# cpLeoNode_V3_0.net
KiCad netlist of a schematic drawn in EAGLE
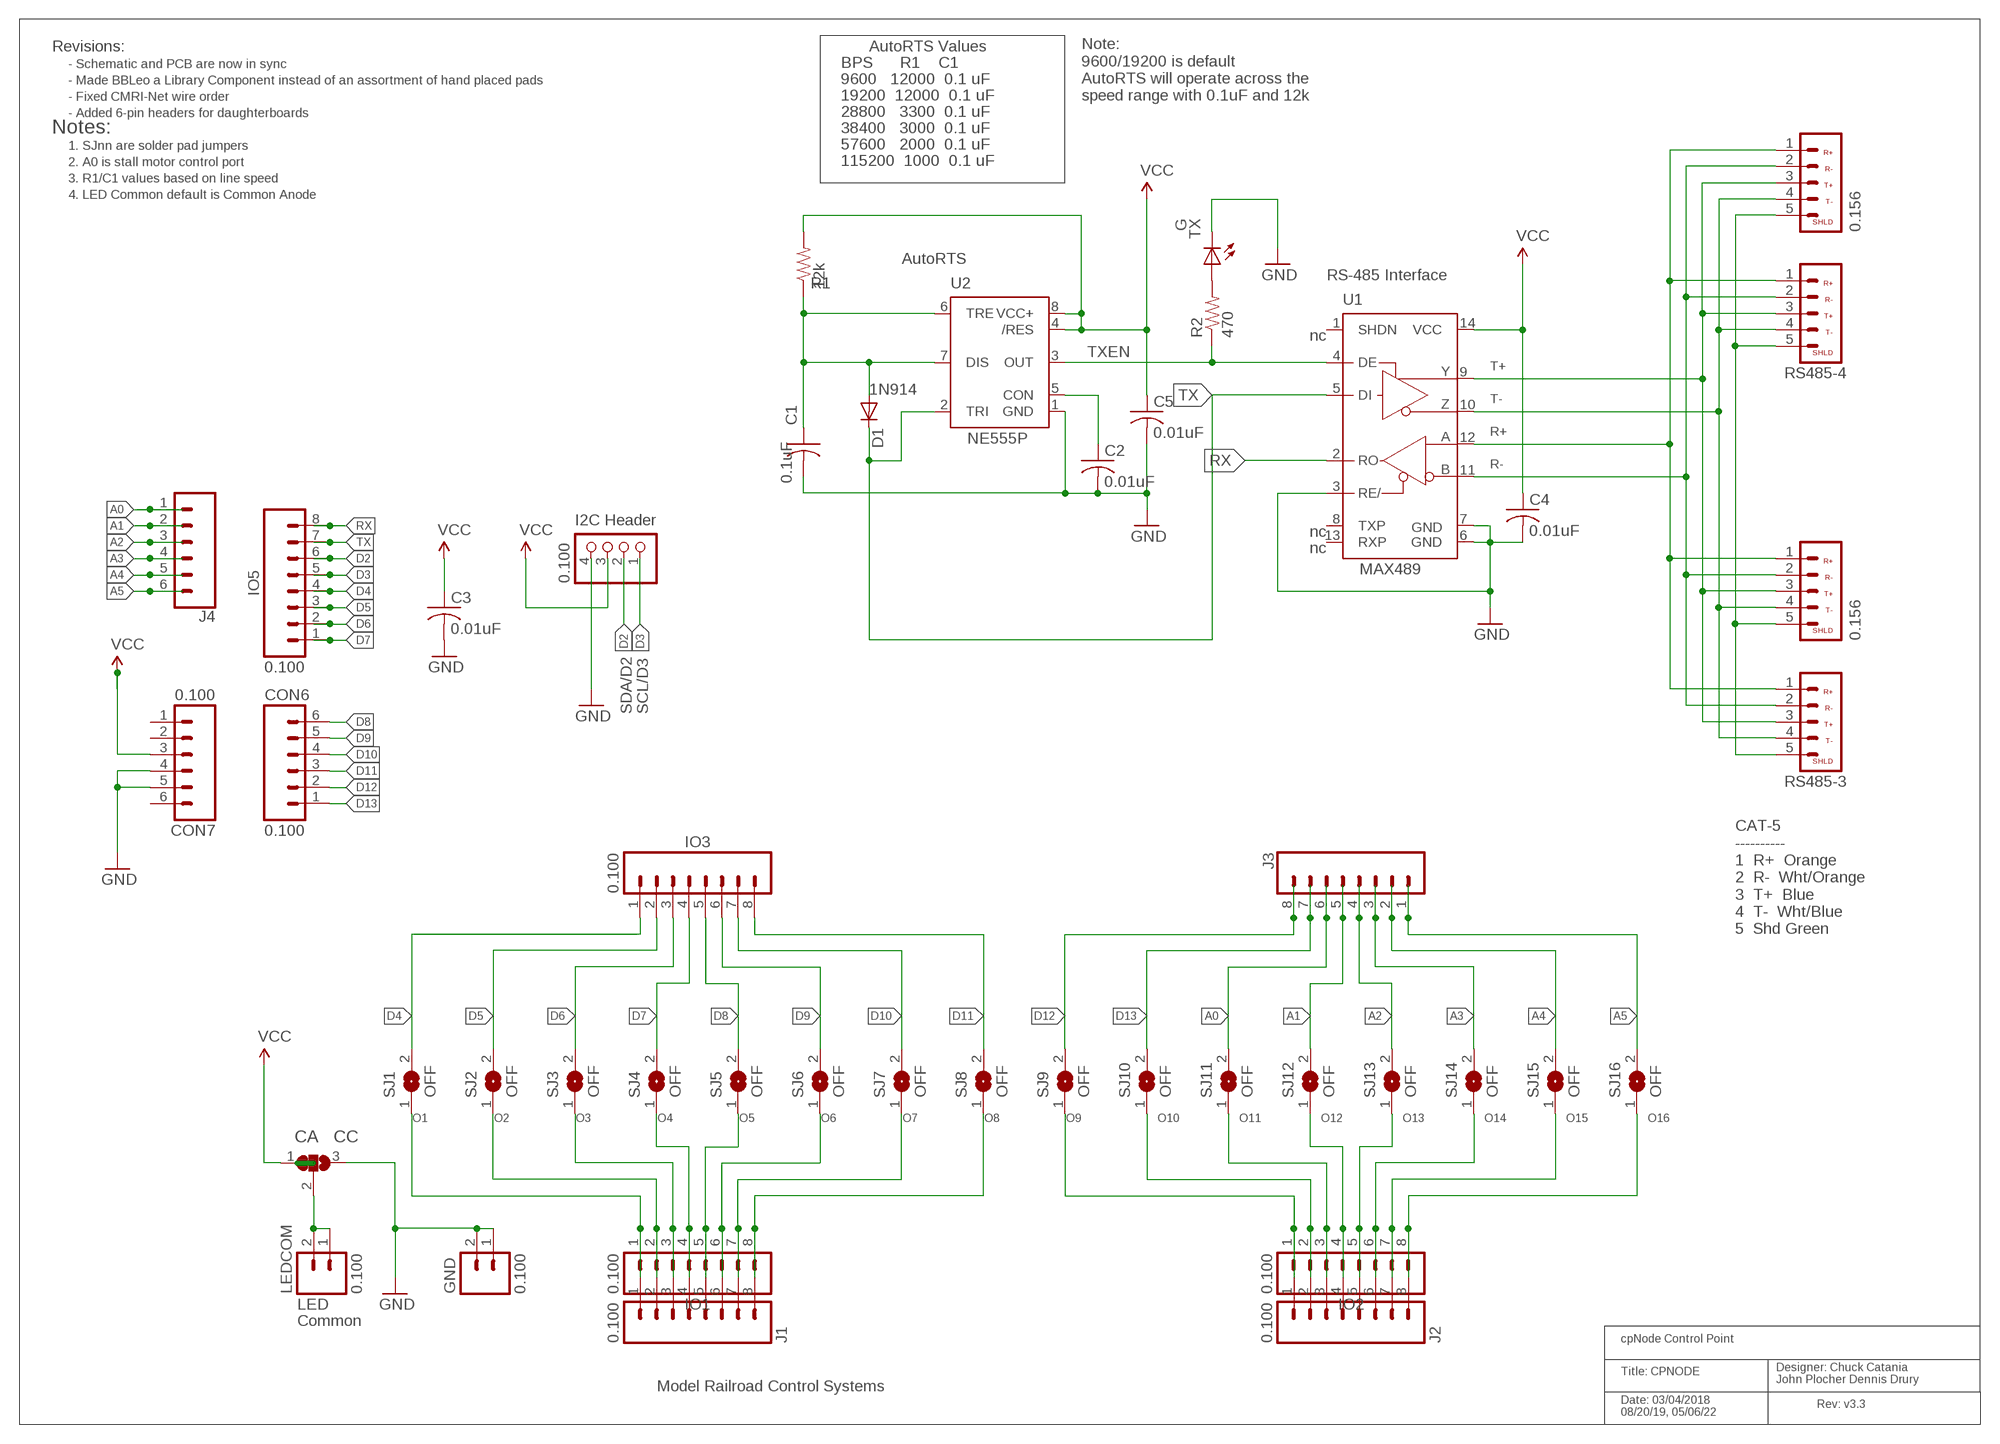
[diagram p0: schematic, sheet 1]

(export (version "E")
  (design (tool "Eeschema 10.0.6"))
  (components
    (comp (ref "C1")
      (value "0.1uF")
      (footprint "eagle-import:C-PTH-0.100")
      (libsource (lib "eagle-import") (part "CAPPTH2"))
    )
    (comp (ref "C2")
      (value "0.01uF")
      (footprint "eagle-import:C-PTH-0.100")
      (libsource (lib "eagle-import") (part "CAPPTH2"))
    )
    (comp (ref "C3")
      (value "0.01uF")
      (footprint "eagle-import:C-PTH-0.100")
      (libsource (lib "eagle-import") (part "CAPPTH2"))
    )
    (comp (ref "C4")
      (value "0.01uF")
      (footprint "eagle-import:C-PTH-0.100")
      (libsource (lib "eagle-import") (part "CAPPTH2"))
    )
    (comp (ref "C5")
      (value "0.01uF")
      (footprint "eagle-import:C-PTH-0.100")
      (libsource (lib "eagle-import") (part "CAPPTH2"))
    )
    (comp (ref "CON6")
      (value "0.100")
      (footprint "eagle-import:1X06-SIP_LOCK")
      (libsource (lib "eagle-import") (part "CONNECTOR-M06SIP_LOCK"))
    )
    (comp (ref "CON7")
      (value "0.100")
      (footprint "eagle-import:1X06-SIP_LOCK")
      (libsource (lib "eagle-import") (part "CONNECTOR-M06SIP_LOCK"))
    )
    (comp (ref "D1")
      (value "1N4148")
      (footprint "eagle-import:DIODE-1N4148")
      (libsource (lib "eagle-import") (part "DIODE1N4148"))
    )
    (comp (ref "GND")
      (value "0.100")
      (footprint "eagle-import:MOLEX-1X2_LOCK")
      (libsource (lib "eagle-import") (part "M02POLAR_LOCK"))
    )
    (comp (ref "I2CHDR")
      (value "0.100")
      (footprint "eagle-import:1X04_90")
      (libsource (lib "eagle-import") (part "PINHD-1X4/90"))
    )
    (comp (ref "IO1")
      (value "0.100")
      (footprint "eagle-import:1X08")
      (libsource (lib "eagle-import") (part "M081X08"))
    )
    (comp (ref "IO2")
      (value "0.100")
      (footprint "eagle-import:1X08")
      (libsource (lib "eagle-import") (part "M081X08"))
    )
    (comp (ref "IO3")
      (value "0.100")
      (footprint "eagle-import:1X08")
      (libsource (lib "eagle-import") (part "M081X08"))
    )
    (comp (ref "IO5")
      (value "0.100")
      (footprint "eagle-import:1X08")
      (libsource (lib "eagle-import") (part "M081X08"))
    )
    (comp (ref "J1")
      (value "0.100")
      (footprint "eagle-import:1X08_LOCK_LONGPADS")
      (libsource (lib "eagle-import") (part "CONNECTOR-M08LOCK_LONGPADS"))
    )
    (comp (ref "J2")
      (value "0.100")
      (footprint "eagle-import:1X08_LOCK_LONGPADS")
      (libsource (lib "eagle-import") (part "CONNECTOR-M08LOCK_LONGPADS"))
    )
    (comp (ref "J3")
      (value "CONN_08\"")
      (footprint "eagle-import:1X08")
      (libsource (lib "eagle-import") (part "CONN_08{dblquote}"))
    )
    (comp (ref "J4")
      (value "CONN_06SILK_FEMALE_PTH")
      (footprint "eagle-import:1X06")
      (libsource (lib "eagle-import") (part "CONN_06SILK_FEMALE_PTH"))
    )
    (comp (ref "LEDCOM")
      (value "0.100")
      (footprint "eagle-import:MOLEX-1X2_LOCK")
      (libsource (lib "eagle-import") (part "M02POLAR_LOCK"))
    )
    (comp (ref "P1")
      (value "CA CC")
      (footprint "eagle-import:3P-SMD-2X4.8")
      (libsource (lib "eagle-import") (part "PAD-SOLDERJUMPER-2WAYT"))
    )
    (comp (ref "R1")
      (value "12k")
      (footprint "eagle-import:AXIAL-0.4-RES")
      (libsource (lib "eagle-import") (part "RPTH04"))
    )
    (comp (ref "R2")
      (value "470")
      (footprint "eagle-import:AXIAL-0.4-RES")
      (libsource (lib "eagle-import") (part "RPTH04"))
    )
    (comp (ref "RS485-1")
      (value "0.156")
      (footprint "eagle-import:KK-156-5")
      (libsource (lib "eagle-import") (part "CONNECTOR-CMRINET.156"))
    )
    (comp (ref "RS485-2")
      (value "0.156")
      (footprint "eagle-import:KK-156-5")
      (libsource (lib "eagle-import") (part "CONNECTOR-CMRINET.156"))
    )
    (comp (ref "RS485-3")
      (value "3.5mm")
      (footprint "eagle-import:CMRINET-3.5MM")
      (libsource (lib "eagle-import") (part "CONNECTOR-CMRINET3.5MM"))
    )
    (comp (ref "RS485-4")
      (value "3.5mm")
      (footprint "eagle-import:CMRINET-3.5MM")
      (libsource (lib "eagle-import") (part "CONNECTOR-CMRINET3.5MM"))
    )
    (comp (ref "SJ1")
      (value "OFF")
      (footprint "eagle-import:SJ")
      (libsource (lib "eagle-import") (part "SJ"))
    )
    (comp (ref "SJ2")
      (value "OFF")
      (footprint "eagle-import:SJ")
      (libsource (lib "eagle-import") (part "SJ"))
    )
    (comp (ref "SJ3")
      (value "OFF")
      (footprint "eagle-import:SJ")
      (libsource (lib "eagle-import") (part "SJ"))
    )
    (comp (ref "SJ4")
      (value "OFF")
      (footprint "eagle-import:SJ")
      (libsource (lib "eagle-import") (part "SJ"))
    )
    (comp (ref "SJ5")
      (value "OFF")
      (footprint "eagle-import:SJ")
      (libsource (lib "eagle-import") (part "SJ"))
    )
    (comp (ref "SJ6")
      (value "OFF")
      (footprint "eagle-import:SJ")
      (libsource (lib "eagle-import") (part "SJ"))
    )
    (comp (ref "SJ7")
      (value "OFF")
      (footprint "eagle-import:SJ")
      (libsource (lib "eagle-import") (part "SJ"))
    )
    (comp (ref "SJ8")
      (value "OFF")
      (footprint "eagle-import:SJ")
      (libsource (lib "eagle-import") (part "SJ"))
    )
    (comp (ref "SJ9")
      (value "OFF")
      (footprint "eagle-import:SJ")
      (libsource (lib "eagle-import") (part "SJ"))
    )
    (comp (ref "SJ10")
      (value "OFF")
      (footprint "eagle-import:SJ")
      (libsource (lib "eagle-import") (part "SJ"))
    )
    (comp (ref "SJ11")
      (value "OFF")
      (footprint "eagle-import:SJ")
      (libsource (lib "eagle-import") (part "SJ"))
    )
    (comp (ref "SJ12")
      (value "OFF")
      (footprint "eagle-import:SJ")
      (libsource (lib "eagle-import") (part "SJ"))
    )
    (comp (ref "SJ13")
      (value "OFF")
      (footprint "eagle-import:SJ")
      (libsource (lib "eagle-import") (part "SJ"))
    )
    (comp (ref "SJ14")
      (value "OFF")
      (footprint "eagle-import:SJ")
      (libsource (lib "eagle-import") (part "SJ"))
    )
    (comp (ref "SJ15")
      (value "OFF")
      (footprint "eagle-import:SJ")
      (libsource (lib "eagle-import") (part "SJ"))
    )
    (comp (ref "SJ16")
      (value "OFF")
      (footprint "eagle-import:SJ")
      (libsource (lib "eagle-import") (part "SJ"))
    )
    (comp (ref "TX")
      (value "G")
      (footprint "eagle-import:LED3MM")
      (libsource (lib "eagle-import") (part "LEDLED3MM"))
    )
    (comp (ref "U1")
      (value "MAX3465CPD")
      (footprint "eagle-import:DIL14")
      (fields (field (name "MPN") "MAX3465CPD+"))
      (libsource (lib "eagle-import") (part "MAX346PD5C"))
    )
    (comp (ref "U2")
      (value "NE555P")
      (footprint "eagle-import:DIL-08")
      (fields (field (name "MF") "Arrow Electronics") (field (name "MPN") "NE555N"))
      (libsource (lib "eagle-import") (part "NE555P"))
    )
  )
  (nets
    (net (code "1") (name "/O1") (class "Default")
      (node (ref "IO1") (pin "1") (pinfunction "1_1") (pintype "passive"))
      (node (ref "J1") (pin "1") (pinfunction "1_1") (pintype "passive"))
      (node (ref "SJ1") (pin "1") (pinfunction "1_1") (pintype "passive"))
    )
    (net (code "2") (name "/O2") (class "Default")
      (node (ref "IO1") (pin "2") (pinfunction "2_2") (pintype "passive"))
      (node (ref "J1") (pin "2") (pinfunction "2_2") (pintype "passive"))
      (node (ref "SJ2") (pin "1") (pinfunction "1_1") (pintype "passive"))
    )
    (net (code "3") (name "/O3") (class "Default")
      (node (ref "IO1") (pin "3") (pinfunction "3_3") (pintype "passive"))
      (node (ref "J1") (pin "3") (pinfunction "3_3") (pintype "passive"))
      (node (ref "SJ3") (pin "1") (pinfunction "1_1") (pintype "passive"))
    )
    (net (code "4") (name "/O4") (class "Default")
      (node (ref "IO1") (pin "4") (pinfunction "4_4") (pintype "passive"))
      (node (ref "J1") (pin "4") (pinfunction "4_4") (pintype "passive"))
      (node (ref "SJ4") (pin "1") (pinfunction "1_1") (pintype "passive"))
    )
    (net (code "5") (name "/O5") (class "Default")
      (node (ref "IO1") (pin "5") (pinfunction "5_5") (pintype "passive"))
      (node (ref "J1") (pin "5") (pinfunction "5_5") (pintype "passive"))
      (node (ref "SJ5") (pin "1") (pinfunction "1_1") (pintype "passive"))
    )
    (net (code "6") (name "/O6") (class "Default")
      (node (ref "IO1") (pin "6") (pinfunction "6_6") (pintype "passive"))
      (node (ref "J1") (pin "6") (pinfunction "6_6") (pintype "passive"))
      (node (ref "SJ6") (pin "1") (pinfunction "1_1") (pintype "passive"))
    )
    (net (code "7") (name "/O7") (class "Default")
      (node (ref "IO1") (pin "7") (pinfunction "7_7") (pintype "passive"))
      (node (ref "J1") (pin "7") (pinfunction "7_7") (pintype "passive"))
      (node (ref "SJ7") (pin "1") (pinfunction "1_1") (pintype "passive"))
    )
    (net (code "8") (name "/O8") (class "Default")
      (node (ref "IO1") (pin "8") (pinfunction "8_8") (pintype "passive"))
      (node (ref "J1") (pin "8") (pinfunction "8_8") (pintype "passive"))
      (node (ref "SJ8") (pin "1") (pinfunction "1_1") (pintype "passive"))
    )
    (net (code "9") (name "/O9") (class "Default")
      (node (ref "IO2") (pin "1") (pinfunction "1_1") (pintype "passive"))
      (node (ref "J2") (pin "1") (pinfunction "1_1") (pintype "passive"))
      (node (ref "SJ9") (pin "1") (pinfunction "1_1") (pintype "passive"))
    )
    (net (code "10") (name "/O10") (class "Default")
      (node (ref "IO2") (pin "2") (pinfunction "2_2") (pintype "passive"))
      (node (ref "J2") (pin "2") (pinfunction "2_2") (pintype "passive"))
      (node (ref "SJ10") (pin "1") (pinfunction "1_1") (pintype "passive"))
    )
    (net (code "11") (name "/O11") (class "Default")
      (node (ref "IO2") (pin "3") (pinfunction "3_3") (pintype "passive"))
      (node (ref "J2") (pin "3") (pinfunction "3_3") (pintype "passive"))
      (node (ref "SJ11") (pin "1") (pinfunction "1_1") (pintype "passive"))
    )
    (net (code "12") (name "/O12") (class "Default")
      (node (ref "IO2") (pin "4") (pinfunction "4_4") (pintype "passive"))
      (node (ref "J2") (pin "4") (pinfunction "4_4") (pintype "passive"))
      (node (ref "SJ12") (pin "1") (pinfunction "1_1") (pintype "passive"))
    )
    (net (code "13") (name "/O13") (class "Default")
      (node (ref "IO2") (pin "5") (pinfunction "5_5") (pintype "passive"))
      (node (ref "J2") (pin "5") (pinfunction "5_5") (pintype "passive"))
      (node (ref "SJ13") (pin "1") (pinfunction "1_1") (pintype "passive"))
    )
    (net (code "14") (name "/O14") (class "Default")
      (node (ref "IO2") (pin "6") (pinfunction "6_6") (pintype "passive"))
      (node (ref "J2") (pin "6") (pinfunction "6_6") (pintype "passive"))
      (node (ref "SJ14") (pin "1") (pinfunction "1_1") (pintype "passive"))
    )
    (net (code "15") (name "/O15") (class "Default")
      (node (ref "IO2") (pin "7") (pinfunction "7_7") (pintype "passive"))
      (node (ref "J2") (pin "7") (pinfunction "7_7") (pintype "passive"))
      (node (ref "SJ15") (pin "1") (pinfunction "1_1") (pintype "passive"))
    )
    (net (code "16") (name "/O16") (class "Default")
      (node (ref "IO2") (pin "8") (pinfunction "8_8") (pintype "passive"))
      (node (ref "J2") (pin "8") (pinfunction "8_8") (pintype "passive"))
      (node (ref "SJ16") (pin "1") (pinfunction "1_1") (pintype "passive"))
    )
    (net (code "17") (name "A0") (class "Default")
      (node (ref "J3") (pin "6") (pinfunction "6_6") (pintype "passive"))
      (node (ref "J4") (pin "1") (pinfunction "1_1") (pintype "passive"))
      (node (ref "SJ11") (pin "2") (pinfunction "2_2") (pintype "passive"))
    )
    (net (code "18") (name "A1") (class "Default")
      (node (ref "J3") (pin "5") (pinfunction "5_5") (pintype "passive"))
      (node (ref "J4") (pin "2") (pinfunction "2_2") (pintype "passive"))
      (node (ref "SJ12") (pin "2") (pinfunction "2_2") (pintype "passive"))
    )
    (net (code "19") (name "A2") (class "Default")
      (node (ref "J3") (pin "4") (pinfunction "4_4") (pintype "passive"))
      (node (ref "J4") (pin "3") (pinfunction "3_3") (pintype "passive"))
      (node (ref "SJ13") (pin "2") (pinfunction "2_2") (pintype "passive"))
    )
    (net (code "20") (name "A3") (class "Default")
      (node (ref "J3") (pin "3") (pinfunction "3_3") (pintype "passive"))
      (node (ref "J4") (pin "4") (pinfunction "4_4") (pintype "passive"))
      (node (ref "SJ14") (pin "2") (pinfunction "2_2") (pintype "passive"))
    )
    (net (code "21") (name "A4") (class "Default")
      (node (ref "J3") (pin "2") (pinfunction "2_2") (pintype "passive"))
      (node (ref "J4") (pin "5") (pinfunction "5_5") (pintype "passive"))
      (node (ref "SJ15") (pin "2") (pinfunction "2_2") (pintype "passive"))
    )
    (net (code "22") (name "A5") (class "Default")
      (node (ref "J3") (pin "1") (pinfunction "1_1") (pintype "passive"))
      (node (ref "J4") (pin "6") (pinfunction "6_6") (pintype "passive"))
      (node (ref "SJ16") (pin "2") (pinfunction "2_2") (pintype "passive"))
    )
    (net (code "23") (name "D2") (class "Default")
      (node (ref "I2CHDR") (pin "2") (pinfunction "2_2") (pintype "passive"))
      (node (ref "IO5") (pin "6") (pinfunction "6_6") (pintype "passive"))
    )
    (net (code "24") (name "D3") (class "Default")
      (node (ref "I2CHDR") (pin "1") (pinfunction "1_1") (pintype "passive"))
      (node (ref "IO5") (pin "5") (pinfunction "5_5") (pintype "passive"))
    )
    (net (code "25") (name "D4") (class "Default")
      (node (ref "IO3") (pin "1") (pinfunction "1_1") (pintype "passive"))
      (node (ref "IO5") (pin "4") (pinfunction "4_4") (pintype "passive"))
      (node (ref "SJ1") (pin "2") (pinfunction "2_2") (pintype "passive"))
    )
    (net (code "26") (name "D5") (class "Default")
      (node (ref "IO3") (pin "2") (pinfunction "2_2") (pintype "passive"))
      (node (ref "IO5") (pin "3") (pinfunction "3_3") (pintype "passive"))
      (node (ref "SJ2") (pin "2") (pinfunction "2_2") (pintype "passive"))
    )
    (net (code "27") (name "D6") (class "Default")
      (node (ref "IO3") (pin "3") (pinfunction "3_3") (pintype "passive"))
      (node (ref "IO5") (pin "2") (pinfunction "2_2") (pintype "passive"))
      (node (ref "SJ3") (pin "2") (pinfunction "2_2") (pintype "passive"))
    )
    (net (code "28") (name "D7") (class "Default")
      (node (ref "IO3") (pin "4") (pinfunction "4_4") (pintype "passive"))
      (node (ref "IO5") (pin "1") (pinfunction "1_1") (pintype "passive"))
      (node (ref "SJ4") (pin "2") (pinfunction "2_2") (pintype "passive"))
    )
    (net (code "29") (name "D8") (class "Default")
      (node (ref "CON6") (pin "6") (pinfunction "6_6") (pintype "passive"))
      (node (ref "IO3") (pin "5") (pinfunction "5_5") (pintype "passive"))
      (node (ref "SJ5") (pin "2") (pinfunction "2_2") (pintype "passive"))
    )
    (net (code "30") (name "D9") (class "Default")
      (node (ref "CON6") (pin "5") (pinfunction "5_5") (pintype "passive"))
      (node (ref "IO3") (pin "6") (pinfunction "6_6") (pintype "passive"))
      (node (ref "SJ6") (pin "2") (pinfunction "2_2") (pintype "passive"))
    )
    (net (code "31") (name "D10") (class "Default")
      (node (ref "CON6") (pin "4") (pinfunction "4_4") (pintype "passive"))
      (node (ref "IO3") (pin "7") (pinfunction "7_7") (pintype "passive"))
      (node (ref "SJ7") (pin "2") (pinfunction "2_2") (pintype "passive"))
    )
    (net (code "32") (name "D11") (class "Default")
      (node (ref "CON6") (pin "3") (pinfunction "3_3") (pintype "passive"))
      (node (ref "IO3") (pin "8") (pinfunction "8_8") (pintype "passive"))
      (node (ref "SJ8") (pin "2") (pinfunction "2_2") (pintype "passive"))
    )
    (net (code "33") (name "D12") (class "Default")
      (node (ref "CON6") (pin "2") (pinfunction "2_2") (pintype "passive"))
      (node (ref "J3") (pin "8") (pinfunction "8_8") (pintype "passive"))
      (node (ref "SJ9") (pin "2") (pinfunction "2_2") (pintype "passive"))
    )
    (net (code "34") (name "D13") (class "Default")
      (node (ref "CON6") (pin "1") (pinfunction "1_1") (pintype "passive"))
      (node (ref "J3") (pin "7") (pinfunction "7_7") (pintype "passive"))
      (node (ref "SJ10") (pin "2") (pinfunction "2_2") (pintype "passive"))
    )
    (net (code "35") (name "GND") (class "Default")
      (node (ref "C1") (pin "2") (pinfunction "2_2") (pintype "passive"))
      (node (ref "C2") (pin "2") (pinfunction "2_2") (pintype "passive"))
      (node (ref "C3") (pin "2") (pinfunction "2_2") (pintype "passive"))
      (node (ref "C4") (pin "2") (pinfunction "2_2") (pintype "passive"))
      (node (ref "C5") (pin "2") (pinfunction "2_2") (pintype "passive"))
      (node (ref "CON7") (pin "4") (pinfunction "4_4") (pintype "passive"))
      (node (ref "CON7") (pin "5") (pinfunction "5_5") (pintype "passive"))
      (node (ref "GND") (pin "1") (pinfunction "1_1") (pintype "passive"))
      (node (ref "GND") (pin "2") (pinfunction "2_2") (pintype "passive"))
      (node (ref "I2CHDR") (pin "4") (pinfunction "4_4") (pintype "passive"))
      (node (ref "P1") (pin "3") (pinfunction "3_3") (pintype "passive"))
      (node (ref "TX") (pin "K") (pinfunction "C_K") (pintype "passive"))
      (node (ref "U1") (pin "3") (pinfunction "RE/_3") (pintype "input"))
      (node (ref "U1") (pin "6") (pinfunction "GND_6") (pintype "power_in"))
      (node (ref "U1") (pin "7") (pinfunction "GND_7") (pintype "power_in"))
      (node (ref "U2") (pin "1") (pinfunction "GND_1") (pintype "power_in"))
    )
    (net (code "36") (name "Net-(LEDCOM-Pad1)") (class "Default")
      (node (ref "LEDCOM") (pin "1") (pinfunction "1_1") (pintype "passive"))
      (node (ref "LEDCOM") (pin "2") (pinfunction "2_2") (pintype "passive"))
      (node (ref "P1") (pin "2") (pinfunction "2_2") (pintype "passive"))
    )
    (net (code "37") (name "Net-(R1-1)") (class "Default")
      (node (ref "C1") (pin "1") (pinfunction "1_1") (pintype "passive"))
      (node (ref "D1") (pin "A") (pinfunction "A_A") (pintype "passive"))
      (node (ref "R1") (pin "P$1") (pinfunction "1_P$1") (pintype "passive"))
      (node (ref "U2") (pin "6") (pinfunction "TRE_6") (pintype "input"))
      (node (ref "U2") (pin "7") (pinfunction "DIS_7") (pintype "input"))
    )
    (net (code "38") (name "Net-(R2-1)") (class "Default")
      (node (ref "R2") (pin "P$1") (pinfunction "1_P$1") (pintype "passive"))
      (node (ref "U1") (pin "4") (pinfunction "DE_4") (pintype "input"))
      (node (ref "U2") (pin "3") (pinfunction "OUT_3") (pintype "output"))
    )
    (net (code "39") (name "Net-(R2-2)") (class "Default")
      (node (ref "R2") (pin "P$2") (pinfunction "2_P$2") (pintype "passive"))
      (node (ref "TX") (pin "A") (pinfunction "A_A") (pintype "passive"))
    )
    (net (code "40") (name "Net-(RS485-1-Pad5)") (class "Default")
      (node (ref "RS485-1") (pin "5") (pinfunction "5_5") (pintype "passive"))
      (node (ref "RS485-2") (pin "5") (pinfunction "5_5") (pintype "passive"))
      (node (ref "RS485-3") (pin "5") (pinfunction "5_5") (pintype "passive"))
      (node (ref "RS485-4") (pin "5") (pinfunction "5_5") (pintype "passive"))
    )
    (net (code "41") (name "Net-(U1-A)") (class "Default")
      (node (ref "RS485-1") (pin "1") (pinfunction "1_1") (pintype "passive"))
      (node (ref "RS485-2") (pin "1") (pinfunction "1_1") (pintype "passive"))
      (node (ref "RS485-3") (pin "1") (pinfunction "1_1") (pintype "passive"))
      (node (ref "RS485-4") (pin "1") (pinfunction "1_1") (pintype "passive"))
      (node (ref "U1") (pin "12") (pinfunction "A_12") (pintype "input"))
    )
    (net (code "42") (name "Net-(U1-B)") (class "Default")
      (node (ref "RS485-1") (pin "2") (pinfunction "2_2") (pintype "passive"))
      (node (ref "RS485-2") (pin "2") (pinfunction "2_2") (pintype "passive"))
      (node (ref "RS485-3") (pin "2") (pinfunction "2_2") (pintype "passive"))
      (node (ref "RS485-4") (pin "2") (pinfunction "2_2") (pintype "passive"))
      (node (ref "U1") (pin "11") (pinfunction "B_11") (pintype "input"))
    )
    (net (code "43") (name "Net-(U1-Y)") (class "Default")
      (node (ref "RS485-1") (pin "3") (pinfunction "3_3") (pintype "passive"))
      (node (ref "RS485-2") (pin "3") (pinfunction "3_3") (pintype "passive"))
      (node (ref "RS485-3") (pin "3") (pinfunction "3_3") (pintype "passive"))
      (node (ref "RS485-4") (pin "3") (pinfunction "3_3") (pintype "passive"))
      (node (ref "U1") (pin "9") (pinfunction "Y_9") (pintype "output"))
    )
    (net (code "44") (name "Net-(U1-Z)") (class "Default")
      (node (ref "RS485-1") (pin "4") (pinfunction "4_4") (pintype "passive"))
      (node (ref "RS485-2") (pin "4") (pinfunction "4_4") (pintype "passive"))
      (node (ref "RS485-3") (pin "4") (pinfunction "4_4") (pintype "passive"))
      (node (ref "RS485-4") (pin "4") (pinfunction "4_4") (pintype "passive"))
      (node (ref "U1") (pin "10") (pinfunction "Z_10") (pintype "output"))
    )
    (net (code "45") (name "Net-(U2-CON)") (class "Default")
      (node (ref "C2") (pin "1") (pinfunction "1_1") (pintype "passive"))
      (node (ref "U2") (pin "5") (pinfunction "CON_5") (pintype "input"))
    )
    (net (code "46") (name "RX") (class "Default")
      (node (ref "IO5") (pin "8") (pinfunction "8_8") (pintype "passive"))
      (node (ref "U1") (pin "2") (pinfunction "RO_2") (pintype "output"))
    )
    (net (code "47") (name "TX") (class "Default")
      (node (ref "D1") (pin "C") (pinfunction "C_C") (pintype "passive"))
      (node (ref "IO5") (pin "7") (pinfunction "7_7") (pintype "passive"))
      (node (ref "U1") (pin "5") (pinfunction "DI_5") (pintype "input"))
      (node (ref "U2") (pin "2") (pinfunction "TRI_2") (pintype "input"))
    )
    (net (code "48") (name "VCC") (class "Default")
      (node (ref "C3") (pin "1") (pinfunction "1_1") (pintype "passive"))
      (node (ref "C4") (pin "1") (pinfunction "1_1") (pintype "passive"))
      (node (ref "C5") (pin "1") (pinfunction "1_1") (pintype "passive"))
      (node (ref "CON7") (pin "3") (pinfunction "3_3") (pintype "passive"))
      (node (ref "I2CHDR") (pin "3") (pinfunction "3_3") (pintype "passive"))
      (node (ref "P1") (pin "1") (pinfunction "1_1") (pintype "passive"))
      (node (ref "R1") (pin "P$2") (pinfunction "2_P$2") (pintype "passive"))
      (node (ref "U1") (pin "14") (pinfunction "VCC_14") (pintype "power_in"))
      (node (ref "U2") (pin "4") (pinfunction "/RES_4") (pintype "input"))
      (node (ref "U2") (pin "8") (pinfunction "VCC+_8") (pintype "power_in"))
    )
    (net (code "49") (name "unconnected-(CON7-Pad1)") (class "Default")
      (node (ref "CON7") (pin "1") (pinfunction "1_1") (pintype "passive"))
    )
    (net (code "50") (name "unconnected-(CON7-Pad2)") (class "Default")
      (node (ref "CON7") (pin "2") (pinfunction "2_2") (pintype "passive"))
    )
    (net (code "51") (name "unconnected-(CON7-Pad6)") (class "Default")
      (node (ref "CON7") (pin "6") (pinfunction "6_6") (pintype "passive"))
    )
    (net (code "52") (name "unconnected-(U1-RXP-Pad13)") (class "Default")
      (node (ref "U1") (pin "13") (pinfunction "RXP_13") (pintype "passive"))
    )
    (net (code "53") (name "unconnected-(U1-SHDN-Pad1)") (class "Default")
      (node (ref "U1") (pin "1") (pinfunction "SHDN_1") (pintype "input"))
    )
    (net (code "54") (name "unconnected-(U1-TXP-Pad8)") (class "Default")
      (node (ref "U1") (pin "8") (pinfunction "TXP_8") (pintype "passive"))
    )
  )
)
